# NodeMCU_Extn.net
KiCad netlist of a schematic drawn in EAGLE
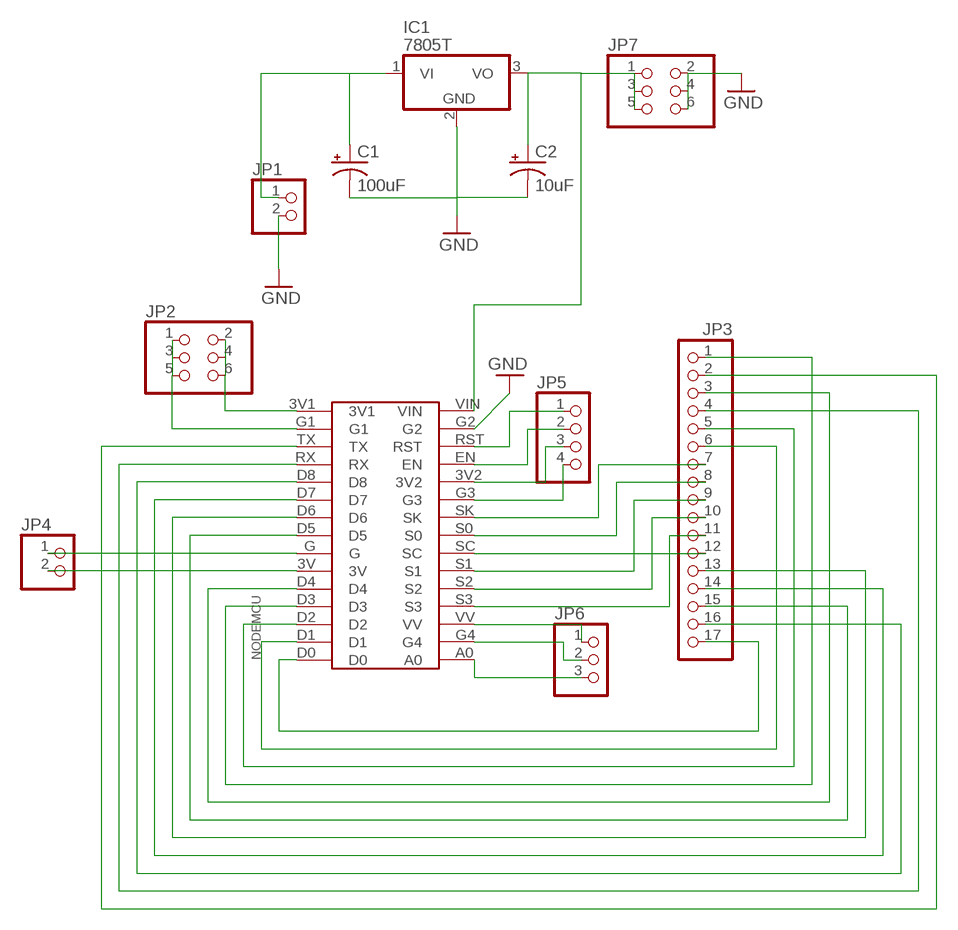
[diagram p0: schematic, sheet 1]

(export (version "E")
  (design (tool "Eeschema 10.0.6"))
  (components
    (comp (ref "C1")
      (value "100uF")
      (footprint "eagle-import:CPOL-RADIAL-2.5MM-5MM")
      (libsource (lib "eagle-import") (part "10UF-POLAR-RADIAL-2.5MM-25V-20%"))
    )
    (comp (ref "C2")
      (value "10uF")
      (footprint "eagle-import:CPOL-RADIAL-2.5MM-5MM")
      (libsource (lib "eagle-import") (part "10UF-POLAR-RADIAL-2.5MM-25V-20%"))
    )
    (comp (ref "IC1")
      (value "7805T")
      (footprint "eagle-import:TO220H")
      (libsource (lib "eagle-import") (part "78T05"))
    )
    (comp (ref "JP1")
      (value "PINHD-1X2")
      (footprint "eagle-import:1X02")
      (libsource (lib "eagle-import") (part "PINHD-1X2"))
    )
    (comp (ref "JP2")
      (value "PINHD-2X3")
      (footprint "eagle-import:2X03")
      (libsource (lib "eagle-import") (part "PINHD-2X3"))
    )
    (comp (ref "JP3")
      (value "PINHD-1X17")
      (footprint "eagle-import:1X17")
      (libsource (lib "eagle-import") (part "PINHD-1X17"))
    )
    (comp (ref "JP4")
      (value "PINHD-1X2")
      (footprint "eagle-import:1X02")
      (libsource (lib "eagle-import") (part "PINHD-1X2"))
    )
    (comp (ref "JP5")
      (value "PINHD-1X4")
      (footprint "eagle-import:1X04")
      (libsource (lib "eagle-import") (part "PINHD-1X4"))
    )
    (comp (ref "JP6")
      (value "PINHD-1X3")
      (footprint "eagle-import:1X03")
      (libsource (lib "eagle-import") (part "PINHD-1X3"))
    )
    (comp (ref "JP7")
      (value "PINHD-2X3")
      (footprint "eagle-import:2X03")
      (libsource (lib "eagle-import") (part "PINHD-2X3"))
    )
    (comp (ref "NODEMCU")
      (value "LOLIN")
      (footprint "eagle-import:LOLIN")
      (libsource (lib "eagle-import") (part "LOLIN"))
    )
  )
  (nets
    (net (code "1") (name "GND") (class "Default")
      (node (ref "C1") (pin "2") (pinfunction "-_2") (pintype "passive"))
      (node (ref "C2") (pin "2") (pinfunction "-_2") (pintype "passive"))
      (node (ref "IC1") (pin "2") (pinfunction "GND_2") (pintype "passive"))
      (node (ref "JP1") (pin "2") (pinfunction "2_2") (pintype "passive"))
      (node (ref "JP7") (pin "2") (pinfunction "2_2") (pintype "passive"))
      (node (ref "JP7") (pin "4") (pinfunction "4_4") (pintype "passive"))
      (node (ref "JP7") (pin "6") (pinfunction "6_6") (pintype "passive"))
      (node (ref "NODEMCU") (pin "G2") (pinfunction "G2_G2") (pintype "bidirectional"))
    )
    (net (code "2") (name "Net-(C1-+)") (class "Default")
      (node (ref "C1") (pin "1") (pinfunction "+_1") (pintype "passive"))
      (node (ref "IC1") (pin "1") (pinfunction "VI_1") (pintype "input"))
      (node (ref "JP1") (pin "1") (pinfunction "1_1") (pintype "passive"))
    )
    (net (code "3") (name "Net-(C2-+)") (class "Default")
      (node (ref "C2") (pin "1") (pinfunction "+_1") (pintype "passive"))
      (node (ref "IC1") (pin "3") (pinfunction "VO_3") (pintype "passive"))
      (node (ref "JP7") (pin "1") (pinfunction "1_1") (pintype "passive"))
      (node (ref "JP7") (pin "3") (pinfunction "3_3") (pintype "passive"))
      (node (ref "JP7") (pin "5") (pinfunction "5_5") (pintype "passive"))
      (node (ref "NODEMCU") (pin "VIN") (pinfunction "VIN_VIN") (pintype "bidirectional"))
    )
    (net (code "4") (name "Net-(JP2-Pad1)") (class "Default")
      (node (ref "JP2") (pin "1") (pinfunction "1_1") (pintype "passive"))
      (node (ref "JP2") (pin "3") (pinfunction "3_3") (pintype "passive"))
      (node (ref "JP2") (pin "5") (pinfunction "5_5") (pintype "passive"))
      (node (ref "NODEMCU") (pin "G1") (pinfunction "G1_G1") (pintype "bidirectional"))
    )
    (net (code "5") (name "Net-(JP2-Pad2)") (class "Default")
      (node (ref "JP2") (pin "2") (pinfunction "2_2") (pintype "passive"))
      (node (ref "JP2") (pin "4") (pinfunction "4_4") (pintype "passive"))
      (node (ref "JP2") (pin "6") (pinfunction "6_6") (pintype "passive"))
      (node (ref "NODEMCU") (pin "3V1") (pinfunction "3V1_3V1") (pintype "bidirectional"))
    )
    (net (code "6") (name "Net-(JP3-Pad1)") (class "Default")
      (node (ref "JP3") (pin "1") (pinfunction "1_1") (pintype "passive"))
      (node (ref "NODEMCU") (pin "D3") (pinfunction "D3_D3") (pintype "bidirectional"))
    )
    (net (code "7") (name "Net-(JP3-Pad2)") (class "Default")
      (node (ref "JP3") (pin "2") (pinfunction "2_2") (pintype "passive"))
      (node (ref "NODEMCU") (pin "TX") (pinfunction "TX_TX") (pintype "bidirectional"))
    )
    (net (code "8") (name "Net-(JP3-Pad3)") (class "Default")
      (node (ref "JP3") (pin "3") (pinfunction "3_3") (pintype "passive"))
      (node (ref "NODEMCU") (pin "D4") (pinfunction "D4_D4") (pintype "bidirectional"))
    )
    (net (code "9") (name "Net-(JP3-Pad4)") (class "Default")
      (node (ref "JP3") (pin "4") (pinfunction "4_4") (pintype "passive"))
      (node (ref "NODEMCU") (pin "RX") (pinfunction "RX_RX") (pintype "bidirectional"))
    )
    (net (code "10") (name "Net-(JP3-Pad5)") (class "Default")
      (node (ref "JP3") (pin "5") (pinfunction "5_5") (pintype "passive"))
      (node (ref "NODEMCU") (pin "D2") (pinfunction "D2_D2") (pintype "bidirectional"))
    )
    (net (code "11") (name "Net-(JP3-Pad6)") (class "Default")
      (node (ref "JP3") (pin "6") (pinfunction "6_6") (pintype "passive"))
      (node (ref "NODEMCU") (pin "D1") (pinfunction "D1_D1") (pintype "bidirectional"))
    )
    (net (code "12") (name "Net-(JP3-Pad7)") (class "Default")
      (node (ref "JP3") (pin "7") (pinfunction "7_7") (pintype "passive"))
      (node (ref "NODEMCU") (pin "SK") (pinfunction "SK_SK") (pintype "bidirectional"))
    )
    (net (code "13") (name "Net-(JP3-Pad8)") (class "Default")
      (node (ref "JP3") (pin "8") (pinfunction "8_8") (pintype "passive"))
      (node (ref "NODEMCU") (pin "S0") (pinfunction "S0_S0") (pintype "bidirectional"))
    )
    (net (code "14") (name "Net-(JP3-Pad9)") (class "Default")
      (node (ref "JP3") (pin "9") (pinfunction "9_9") (pintype "passive"))
      (node (ref "NODEMCU") (pin "S1") (pinfunction "S1_S1") (pintype "bidirectional"))
    )
    (net (code "15") (name "Net-(JP3-Pad10)") (class "Default")
      (node (ref "JP3") (pin "10") (pinfunction "10_10") (pintype "passive"))
      (node (ref "NODEMCU") (pin "S2") (pinfunction "S2_S2") (pintype "bidirectional"))
    )
    (net (code "16") (name "Net-(JP3-Pad11)") (class "Default")
      (node (ref "JP3") (pin "11") (pinfunction "11_11") (pintype "passive"))
      (node (ref "NODEMCU") (pin "S3") (pinfunction "S3_S3") (pintype "bidirectional"))
    )
    (net (code "17") (name "Net-(JP3-Pad12)") (class "Default")
      (node (ref "JP3") (pin "12") (pinfunction "12_12") (pintype "passive"))
      (node (ref "NODEMCU") (pin "SC") (pinfunction "SC_SC") (pintype "bidirectional"))
    )
    (net (code "18") (name "Net-(JP3-Pad13)") (class "Default")
      (node (ref "JP3") (pin "13") (pinfunction "13_13") (pintype "passive"))
      (node (ref "NODEMCU") (pin "D6") (pinfunction "D6_D6") (pintype "bidirectional"))
    )
    (net (code "19") (name "Net-(JP3-Pad14)") (class "Default")
      (node (ref "JP3") (pin "14") (pinfunction "14_14") (pintype "passive"))
      (node (ref "NODEMCU") (pin "D7") (pinfunction "D7_D7") (pintype "bidirectional"))
    )
    (net (code "20") (name "Net-(JP3-Pad15)") (class "Default")
      (node (ref "JP3") (pin "15") (pinfunction "15_15") (pintype "passive"))
      (node (ref "NODEMCU") (pin "D5") (pinfunction "D5_D5") (pintype "bidirectional"))
    )
    (net (code "21") (name "Net-(JP3-Pad16)") (class "Default")
      (node (ref "JP3") (pin "16") (pinfunction "16_16") (pintype "passive"))
      (node (ref "NODEMCU") (pin "D8") (pinfunction "D8_D8") (pintype "bidirectional"))
    )
    (net (code "22") (name "Net-(JP3-Pad17)") (class "Default")
      (node (ref "JP3") (pin "17") (pinfunction "17_17") (pintype "passive"))
      (node (ref "NODEMCU") (pin "D0") (pinfunction "D0_D0") (pintype "bidirectional"))
    )
    (net (code "23") (name "Net-(JP4-Pad1)") (class "Default")
      (node (ref "JP4") (pin "1") (pinfunction "1_1") (pintype "passive"))
      (node (ref "NODEMCU") (pin "G") (pinfunction "G_G") (pintype "bidirectional"))
    )
    (net (code "24") (name "Net-(JP4-Pad2)") (class "Default")
      (node (ref "JP4") (pin "2") (pinfunction "2_2") (pintype "passive"))
      (node (ref "NODEMCU") (pin "3V") (pinfunction "3V_3V") (pintype "bidirectional"))
    )
    (net (code "25") (name "Net-(JP5-Pad1)") (class "Default")
      (node (ref "JP5") (pin "1") (pinfunction "1_1") (pintype "passive"))
      (node (ref "NODEMCU") (pin "RST") (pinfunction "RST_RST") (pintype "bidirectional"))
    )
    (net (code "26") (name "Net-(JP5-Pad2)") (class "Default")
      (node (ref "JP5") (pin "2") (pinfunction "2_2") (pintype "passive"))
      (node (ref "NODEMCU") (pin "EN") (pinfunction "EN_EN") (pintype "bidirectional"))
    )
    (net (code "27") (name "Net-(JP5-Pad3)") (class "Default")
      (node (ref "JP5") (pin "3") (pinfunction "3_3") (pintype "passive"))
      (node (ref "NODEMCU") (pin "3V2") (pinfunction "3V2_3V2") (pintype "bidirectional"))
    )
    (net (code "28") (name "Net-(JP5-Pad4)") (class "Default")
      (node (ref "JP5") (pin "4") (pinfunction "4_4") (pintype "passive"))
      (node (ref "NODEMCU") (pin "G3") (pinfunction "G3_G3") (pintype "bidirectional"))
    )
    (net (code "29") (name "Net-(JP6-Pad1)") (class "Default")
      (node (ref "JP6") (pin "1") (pinfunction "1_1") (pintype "passive"))
      (node (ref "NODEMCU") (pin "VV") (pinfunction "VV_VV") (pintype "bidirectional"))
    )
    (net (code "30") (name "Net-(JP6-Pad2)") (class "Default")
      (node (ref "JP6") (pin "2") (pinfunction "2_2") (pintype "passive"))
      (node (ref "NODEMCU") (pin "G4") (pinfunction "G4_G4") (pintype "bidirectional"))
    )
    (net (code "31") (name "Net-(JP6-Pad3)") (class "Default")
      (node (ref "JP6") (pin "3") (pinfunction "3_3") (pintype "passive"))
      (node (ref "NODEMCU") (pin "A0") (pinfunction "A0_A0") (pintype "bidirectional"))
    )
  )
)
